# board.net
KiCad netlist of a schematic drawn in EAGLE
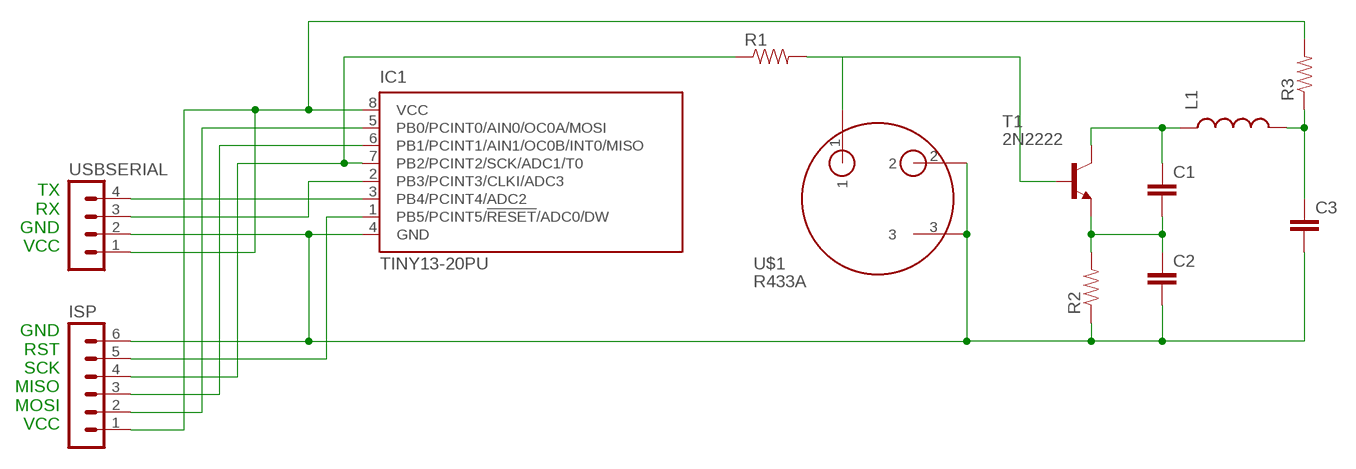
[diagram p0: schematic, sheet 1]

(export (version "E")
  (design (tool "Eeschema 10.0.6"))
  (components
    (comp (ref "C1")
      (value "CAPPTH")
      (footprint "eagle-import:CAP-PTH-SMALL")
      (libsource (lib "eagle-import") (part "CAPPTH"))
    )
    (comp (ref "C2")
      (value "CAPPTH")
      (footprint "eagle-import:CAP-PTH-SMALL")
      (libsource (lib "eagle-import") (part "CAPPTH"))
    )
    (comp (ref "C3")
      (value "CAPPTH1")
      (footprint "eagle-import:CAP-PTH-5MM")
      (libsource (lib "eagle-import") (part "CAPPTH1"))
    )
    (comp (ref "IC1")
      (value "TINY13-20PU")
      (footprint "eagle-import:DIL08")
      (fields (field (name "MPN") "ATTINY13-20PU"))
      (libsource (lib "eagle-import") (part "TINY13PU-20"))
    )
    (comp (ref "ISP")
      (value "MA06-1")
      (footprint "eagle-import:MA06-1")
      (libsource (lib "eagle-import") (part "MA06-1"))
    )
    (comp (ref "L1")
      (value "INDUCTORAXIAL-0.6")
      (footprint "eagle-import:AXIAL-0.6")
      (libsource (lib "eagle-import") (part "INDUCTORAXIAL-0.6"))
    )
    (comp (ref "R1")
      (value "RESISTORAXIAL-0.3")
      (footprint "eagle-import:AXIAL-0.3")
      (libsource (lib "eagle-import") (part "RESISTORAXIAL-0.3"))
    )
    (comp (ref "R2")
      (value "RESISTORAXIAL-0.3")
      (footprint "eagle-import:AXIAL-0.3")
      (libsource (lib "eagle-import") (part "RESISTORAXIAL-0.3"))
    )
    (comp (ref "R3")
      (value "RESISTORAXIAL-0.3")
      (footprint "eagle-import:AXIAL-0.3")
      (libsource (lib "eagle-import") (part "RESISTORAXIAL-0.3"))
    )
    (comp (ref "T1")
      (value "2N2222")
      (footprint "eagle-import:TO92-EBC-OVAL")
      (libsource (lib "eagle-import") (part "2N2222"))
    )
    (comp (ref "U$1")
      (value "R433A")
      (footprint "eagle-import:TO-39")
      (libsource (lib "eagle-import") (part "R433A"))
    )
    (comp (ref "USBSERIAL")
      (value "MA04-1")
      (footprint "eagle-import:MA04-1")
      (libsource (lib "eagle-import") (part "MA04-1"))
    )
  )
  (nets
    (net (code "1") (name "Net-(IC1-GND)") (class "Default")
      (node (ref "C2") (pin "2") (pinfunction "2_2") (pintype "passive"))
      (node (ref "C3") (pin "2") (pinfunction "2_2") (pintype "passive"))
      (node (ref "IC1") (pin "4") (pinfunction "GND_4") (pintype "power_in"))
      (node (ref "ISP") (pin "6") (pinfunction "6_6") (pintype "passive"))
      (node (ref "R2") (pin "P$1") (pinfunction "1_P$1") (pintype "passive"))
      (node (ref "U$1") (pin "2") (pinfunction "2_2") (pintype "bidirectional"))
      (node (ref "U$1") (pin "3") (pinfunction "3_3") (pintype "bidirectional"))
      (node (ref "USBSERIAL") (pin "2") (pinfunction "2_2") (pintype "passive"))
    )
    (net (code "2") (name "Net-(IC1-PB0{slash}PCINT0{slash}AIN0{slash}OC0A{slash}MOSI)") (class "Default")
      (node (ref "IC1") (pin "5") (pinfunction "PB0/PCINT0/AIN0/OC0A/MOSI_5") (pintype "bidirectional"))
      (node (ref "ISP") (pin "2") (pinfunction "2_2") (pintype "passive"))
    )
    (net (code "3") (name "Net-(IC1-PB1{slash}PCINT1{slash}AIN1{slash}OC0B{slash}INT0{slash}MISO)") (class "Default")
      (node (ref "IC1") (pin "6") (pinfunction "PB1/PCINT1/AIN1/OC0B/INT0/MISO_6") (pintype "bidirectional"))
      (node (ref "ISP") (pin "3") (pinfunction "3_3") (pintype "passive"))
    )
    (net (code "4") (name "Net-(IC1-PB2{slash}PCINT2{slash}SCK{slash}ADC1{slash}T0)") (class "Default")
      (node (ref "IC1") (pin "7") (pinfunction "PB2/PCINT2/SCK/ADC1/T0_7") (pintype "bidirectional"))
      (node (ref "ISP") (pin "4") (pinfunction "4_4") (pintype "passive"))
      (node (ref "R1") (pin "P$1") (pinfunction "1_P$1") (pintype "passive"))
    )
    (net (code "5") (name "Net-(IC1-PB3{slash}PCINT3{slash}CLKI{slash}ADC3)") (class "Default")
      (node (ref "IC1") (pin "2") (pinfunction "PB3/PCINT3/CLKI/ADC3_2") (pintype "bidirectional"))
      (node (ref "USBSERIAL") (pin "3") (pinfunction "3_3") (pintype "passive"))
    )
    (net (code "6") (name "Net-(IC1-PB4{slash}PCINT4{slash}ADC2)") (class "Default")
      (node (ref "IC1") (pin "3") (pinfunction "PB4/PCINT4/ADC2_3") (pintype "bidirectional"))
      (node (ref "USBSERIAL") (pin "4") (pinfunction "4_4") (pintype "passive"))
    )
    (net (code "7") (name "Net-(IC1-PB5{slash}PCINT5{slash}~{RESET}{slash}ADC0{slash}DW)") (class "Default")
      (node (ref "IC1") (pin "1") (pinfunction "PB5/PCINT5/~{RESET}/ADC0/DW_1") (pintype "bidirectional"))
      (node (ref "ISP") (pin "5") (pinfunction "5_5") (pintype "passive"))
    )
    (net (code "8") (name "Net-(IC1-VCC)") (class "Default")
      (node (ref "IC1") (pin "8") (pinfunction "VCC_8") (pintype "power_in"))
      (node (ref "ISP") (pin "1") (pinfunction "1_1") (pintype "passive"))
      (node (ref "R3") (pin "P$2") (pinfunction "2_P$2") (pintype "passive"))
      (node (ref "USBSERIAL") (pin "1") (pinfunction "1_1") (pintype "passive"))
    )
    (net (code "9") (name "Net-(L1-1)") (class "Default")
      (node (ref "C1") (pin "1") (pinfunction "1_1") (pintype "passive"))
      (node (ref "L1") (pin "P$1") (pinfunction "1_P$1") (pintype "passive"))
      (node (ref "T1") (pin "C") (pinfunction "C_C") (pintype "passive"))
    )
    (net (code "10") (name "Net-(L1-2)") (class "Default")
      (node (ref "C3") (pin "1") (pinfunction "1_1") (pintype "passive"))
      (node (ref "L1") (pin "P$2") (pinfunction "2_P$2") (pintype "passive"))
      (node (ref "R3") (pin "P$1") (pinfunction "1_P$1") (pintype "passive"))
    )
    (net (code "11") (name "Net-(R1-2)") (class "Default")
      (node (ref "R1") (pin "P$2") (pinfunction "2_P$2") (pintype "passive"))
      (node (ref "T1") (pin "B") (pinfunction "B_B") (pintype "passive"))
      (node (ref "U$1") (pin "1") (pinfunction "1_1") (pintype "bidirectional"))
    )
    (net (code "12") (name "Net-(R2-2)") (class "Default")
      (node (ref "C1") (pin "2") (pinfunction "2_2") (pintype "passive"))
      (node (ref "C2") (pin "1") (pinfunction "1_1") (pintype "passive"))
      (node (ref "R2") (pin "P$2") (pinfunction "2_P$2") (pintype "passive"))
      (node (ref "T1") (pin "E") (pinfunction "E_E") (pintype "passive"))
    )
  )
)
